# SCH_USB-HUB_2025-08-06.net
KiCad netlist of a schematic drawn in EasyEDA
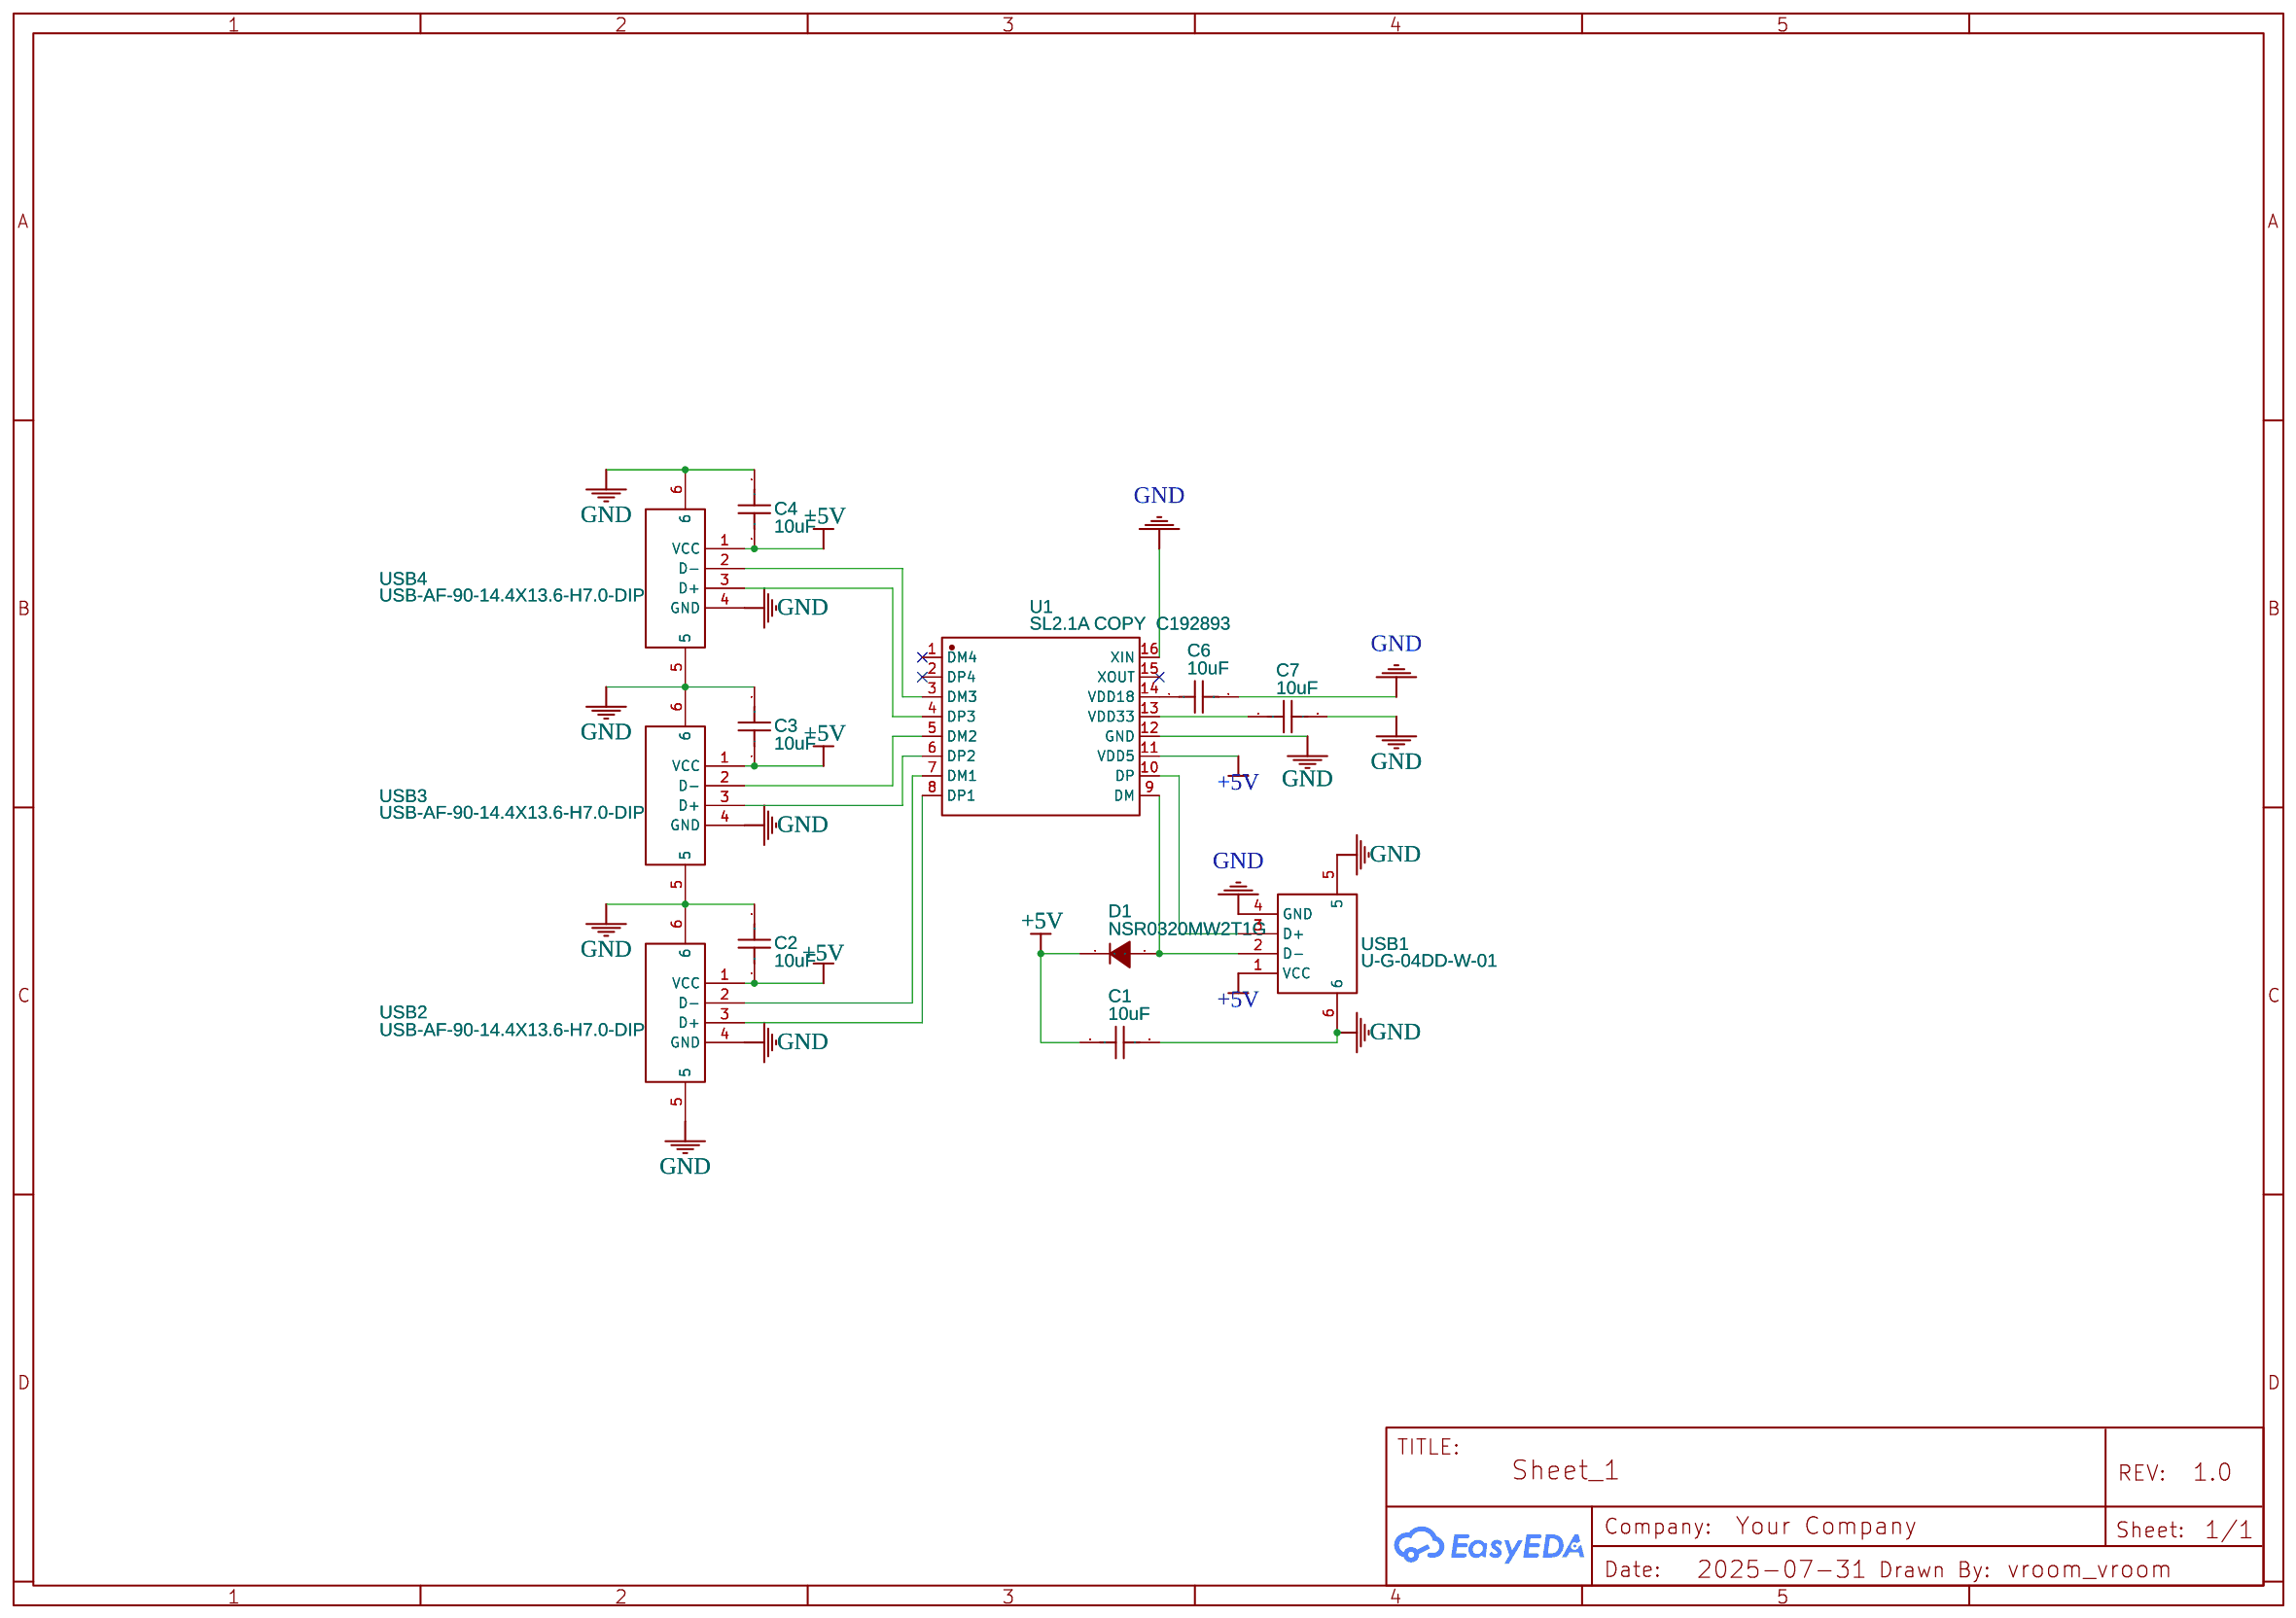
[diagram p0: schematic sheet]

(export (version "E")
  (design (tool "Eeschema 10.0.6"))
  (components
    (comp (ref "C1")
      (value "10uF")
      (fields
        (field (name "Manufacturer Part") "CL10A106KP8NNNC")
        (field (name "Manufacturer") "SAMSUNG(三星)")
      )
      (libsource (lib "") (part "CL10A106KP8NNNC"))
    )
    (comp (ref "C2")
      (value "10uF")
      (fields
        (field (name "Manufacturer Part") "CL10A106KP8NNNC")
        (field (name "Manufacturer") "SAMSUNG(三星)")
      )
      (libsource (lib "") (part "CL10A106KP8NNNC_1"))
    )
    (comp (ref "C3")
      (value "10uF")
      (fields
        (field (name "Manufacturer Part") "CL10A106KP8NNNC")
        (field (name "Manufacturer") "SAMSUNG(三星)")
      )
      (libsource (lib "") (part "CL10A106KP8NNNC_1"))
    )
    (comp (ref "C4")
      (value "10uF")
      (fields
        (field (name "Manufacturer Part") "CL10A106KP8NNNC")
        (field (name "Manufacturer") "SAMSUNG(三星)")
      )
      (libsource (lib "") (part "CL10A106KP8NNNC_1"))
    )
    (comp (ref "C6")
      (value "10uF")
      (fields
        (field (name "Manufacturer Part") "CL10A106KP8NNNC")
        (field (name "Manufacturer") "SAMSUNG(三星)")
      )
      (libsource (lib "") (part "CL10A106KP8NNNC"))
    )
    (comp (ref "C7")
      (value "10uF")
      (fields
        (field (name "Manufacturer Part") "CL10A106KP8NNNC")
        (field (name "Manufacturer") "SAMSUNG(三星)")
      )
      (libsource (lib "") (part "CL10A106KP8NNNC"))
    )
    (comp (ref "D1")
      (value "NSR0320MW2T1G")
      (fields (field (name "Manufacturer") "onsemi(安森美)"))
      (libsource (lib "") (part "NSR0320MW2T1G"))
    )
    (comp (ref "U1")
      (value "SL2.1A COPY  C192893")
      (fields (field (name "Manufacturer Part") "SL2.1A") (field (name "Manufacturer") "CoreChips(和芯润德)"))
      (libsource (lib "") (part "SL2.1A COPY  C192893"))
    )
    (comp (ref "USB1")
      (value "U-G-04DD-W-01")
      (fields (field (name "Manufacturer Part") "U-G-O4DD-W-1") (field (name "Manufacturer") "韩国韩荣"))
      (libsource (lib "") (part "U-G-04DD-W-01"))
    )
    (comp (ref "USB2")
      (value "USB-AF-90-14.4X13.6-H7.0-DIP")
      (fields (field (name "Manufacturer Part") "903-131A1011D10100") (field (name "Manufacturer") "精拓金"))
      (libsource (lib "") (part "USB-AF-90-14.4X13.6-H7.0-DIP"))
    )
    (comp (ref "USB3")
      (value "USB-AF-90-14.4X13.6-H7.0-DIP")
      (fields (field (name "Manufacturer Part") "903-131A1011D10100") (field (name "Manufacturer") "精拓金"))
      (libsource (lib "") (part "USB-AF-90-14.4X13.6-H7.0-DIP"))
    )
    (comp (ref "USB4")
      (value "USB-AF-90-14.4X13.6-H7.0-DIP")
      (fields (field (name "Manufacturer Part") "903-131A1011D10100") (field (name "Manufacturer") "精拓金"))
      (libsource (lib "") (part "USB-AF-90-14.4X13.6-H7.0-DIP"))
    )
  )
  (nets
    (net (code "1") (name "+5V") (class "Default")
      (node (ref "C1") (pin "1") (pinfunction "1_1") (pintype "unspecified"))
      (node (ref "C2") (pin "1") (pinfunction "1_1") (pintype "unspecified"))
      (node (ref "C3") (pin "1") (pinfunction "1_1") (pintype "unspecified"))
      (node (ref "C4") (pin "1") (pinfunction "1_1") (pintype "unspecified"))
      (node (ref "D1") (pin "1") (pinfunction "C_1") (pintype "unspecified"))
      (node (ref "U1") (pin "11") (pinfunction "VDD5_11") (pintype "unspecified"))
      (node (ref "USB1") (pin "1") (pinfunction "VCC_1") (pintype "unspecified"))
      (node (ref "USB2") (pin "1") (pinfunction "VCC_1") (pintype "unspecified"))
      (node (ref "USB3") (pin "1") (pinfunction "VCC_1") (pintype "unspecified"))
      (node (ref "USB4") (pin "1") (pinfunction "VCC_1") (pintype "unspecified"))
    )
    (net (code "2") (name "GND") (class "Default")
      (node (ref "C1") (pin "2") (pinfunction "2_2") (pintype "unspecified"))
      (node (ref "C2") (pin "2") (pinfunction "2_2") (pintype "unspecified"))
      (node (ref "C3") (pin "2") (pinfunction "2_2") (pintype "unspecified"))
      (node (ref "C4") (pin "2") (pinfunction "2_2") (pintype "unspecified"))
      (node (ref "C6") (pin "2") (pinfunction "2_2") (pintype "unspecified"))
      (node (ref "C7") (pin "2") (pinfunction "2_2") (pintype "unspecified"))
      (node (ref "U1") (pin "12") (pinfunction "GND_12") (pintype "unspecified"))
      (node (ref "U1") (pin "16") (pinfunction "XIN_16") (pintype "unspecified"))
      (node (ref "USB1") (pin "4") (pinfunction "GND_4") (pintype "unspecified"))
      (node (ref "USB1") (pin "5") (pinfunction "5_5") (pintype "unspecified"))
      (node (ref "USB1") (pin "6") (pinfunction "6_6") (pintype "unspecified"))
      (node (ref "USB2") (pin "4") (pinfunction "GND_4") (pintype "unspecified"))
      (node (ref "USB2") (pin "5") (pinfunction "5_5") (pintype "unspecified"))
      (node (ref "USB2") (pin "6") (pinfunction "6_6") (pintype "unspecified"))
      (node (ref "USB3") (pin "4") (pinfunction "GND_4") (pintype "unspecified"))
      (node (ref "USB3") (pin "5") (pinfunction "5_5") (pintype "unspecified"))
      (node (ref "USB3") (pin "6") (pinfunction "6_6") (pintype "unspecified"))
      (node (ref "USB4") (pin "4") (pinfunction "GND_4") (pintype "unspecified"))
      (node (ref "USB4") (pin "5") (pinfunction "5_5") (pintype "unspecified"))
      (node (ref "USB4") (pin "6") (pinfunction "6_6") (pintype "unspecified"))
    )
    (net (code "3") (name "Net-(D1-A)") (class "Default")
      (node (ref "D1") (pin "2") (pinfunction "A_2") (pintype "unspecified"))
      (node (ref "U1") (pin "9") (pinfunction "DM_9") (pintype "unspecified"))
      (node (ref "USB1") (pin "2") (pinfunction "D-_2") (pintype "unspecified"))
    )
    (net (code "4") (name "Net-(U1-DM1)") (class "Default")
      (node (ref "U1") (pin "7") (pinfunction "DM1_7") (pintype "unspecified"))
      (node (ref "USB2") (pin "2") (pinfunction "D-_2") (pintype "unspecified"))
    )
    (net (code "5") (name "Net-(U1-DM2)") (class "Default")
      (node (ref "U1") (pin "5") (pinfunction "DM2_5") (pintype "unspecified"))
      (node (ref "USB3") (pin "2") (pinfunction "D-_2") (pintype "unspecified"))
    )
    (net (code "6") (name "Net-(U1-DM3)") (class "Default")
      (node (ref "U1") (pin "3") (pinfunction "DM3_3") (pintype "unspecified"))
      (node (ref "USB4") (pin "2") (pinfunction "D-_2") (pintype "unspecified"))
    )
    (net (code "7") (name "Net-(U1-DP)") (class "Default")
      (node (ref "U1") (pin "10") (pinfunction "DP_10") (pintype "unspecified"))
      (node (ref "USB1") (pin "3") (pinfunction "D+_3") (pintype "unspecified"))
    )
    (net (code "8") (name "Net-(U1-DP1)") (class "Default")
      (node (ref "U1") (pin "8") (pinfunction "DP1_8") (pintype "unspecified"))
      (node (ref "USB2") (pin "3") (pinfunction "D+_3") (pintype "unspecified"))
    )
    (net (code "9") (name "Net-(U1-DP2)") (class "Default")
      (node (ref "U1") (pin "6") (pinfunction "DP2_6") (pintype "unspecified"))
      (node (ref "USB3") (pin "3") (pinfunction "D+_3") (pintype "unspecified"))
    )
    (net (code "10") (name "Net-(U1-DP3)") (class "Default")
      (node (ref "U1") (pin "4") (pinfunction "DP3_4") (pintype "unspecified"))
      (node (ref "USB4") (pin "3") (pinfunction "D+_3") (pintype "unspecified"))
    )
    (net (code "11") (name "Net-(U1-VDD18)") (class "Default")
      (node (ref "C6") (pin "1") (pinfunction "1_1") (pintype "unspecified"))
      (node (ref "U1") (pin "14") (pinfunction "VDD18_14") (pintype "unspecified"))
    )
    (net (code "12") (name "Net-(U1-VDD33)") (class "Default")
      (node (ref "C7") (pin "1") (pinfunction "1_1") (pintype "unspecified"))
      (node (ref "U1") (pin "13") (pinfunction "VDD33_13") (pintype "unspecified"))
    )
    (net (code "13") (name "unconnected-(U1-DM4-Pad1)") (class "Default")
      (node (ref "U1") (pin "1") (pinfunction "DM4_1") (pintype "unspecified+no_connect"))
    )
    (net (code "14") (name "unconnected-(U1-DP4-Pad2)") (class "Default")
      (node (ref "U1") (pin "2") (pinfunction "DP4_2") (pintype "unspecified+no_connect"))
    )
    (net (code "15") (name "unconnected-(U1-XOUT-Pad15)") (class "Default")
      (node (ref "U1") (pin "15") (pinfunction "XOUT_15") (pintype "unspecified+no_connect"))
    )
  )
)
